# Mainboard.net
KiCad netlist of a schematic drawn in EAGLE
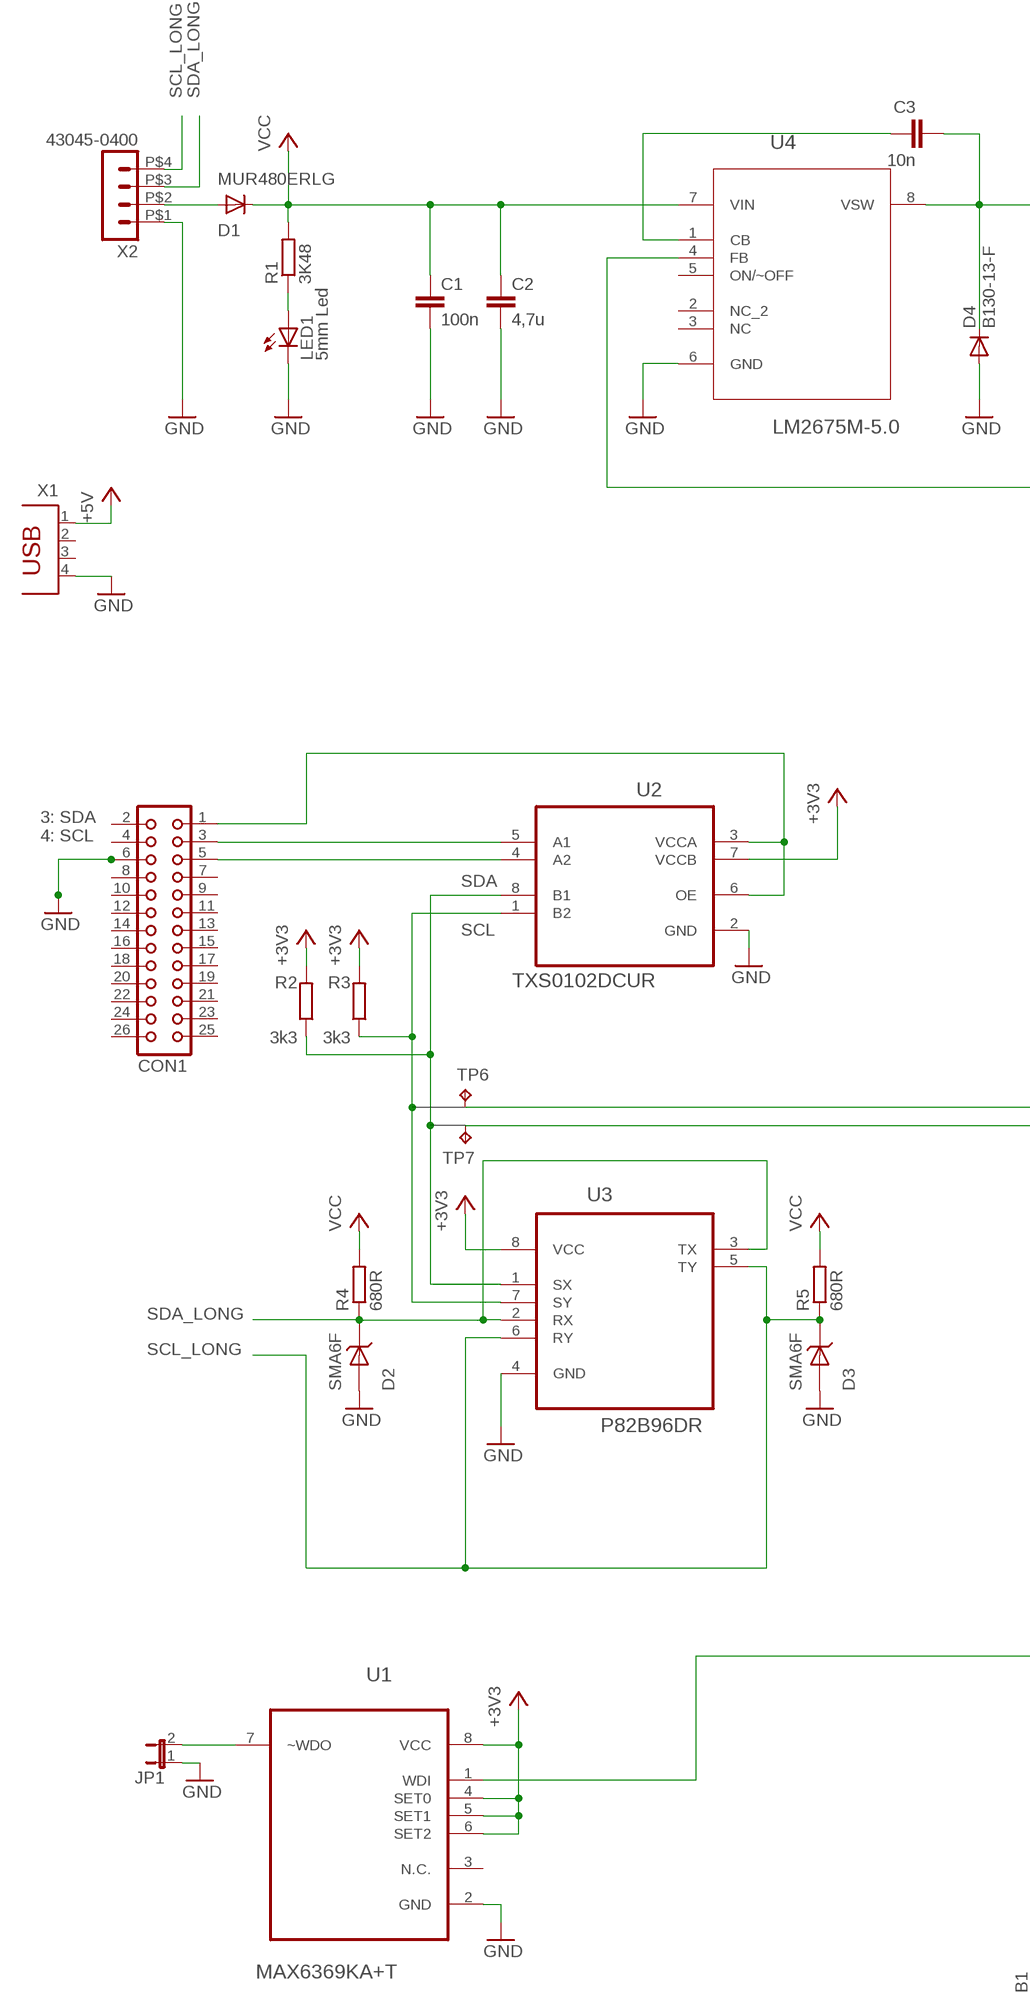
[diagram p0: schematic, sheet 1, part 1 of 2]
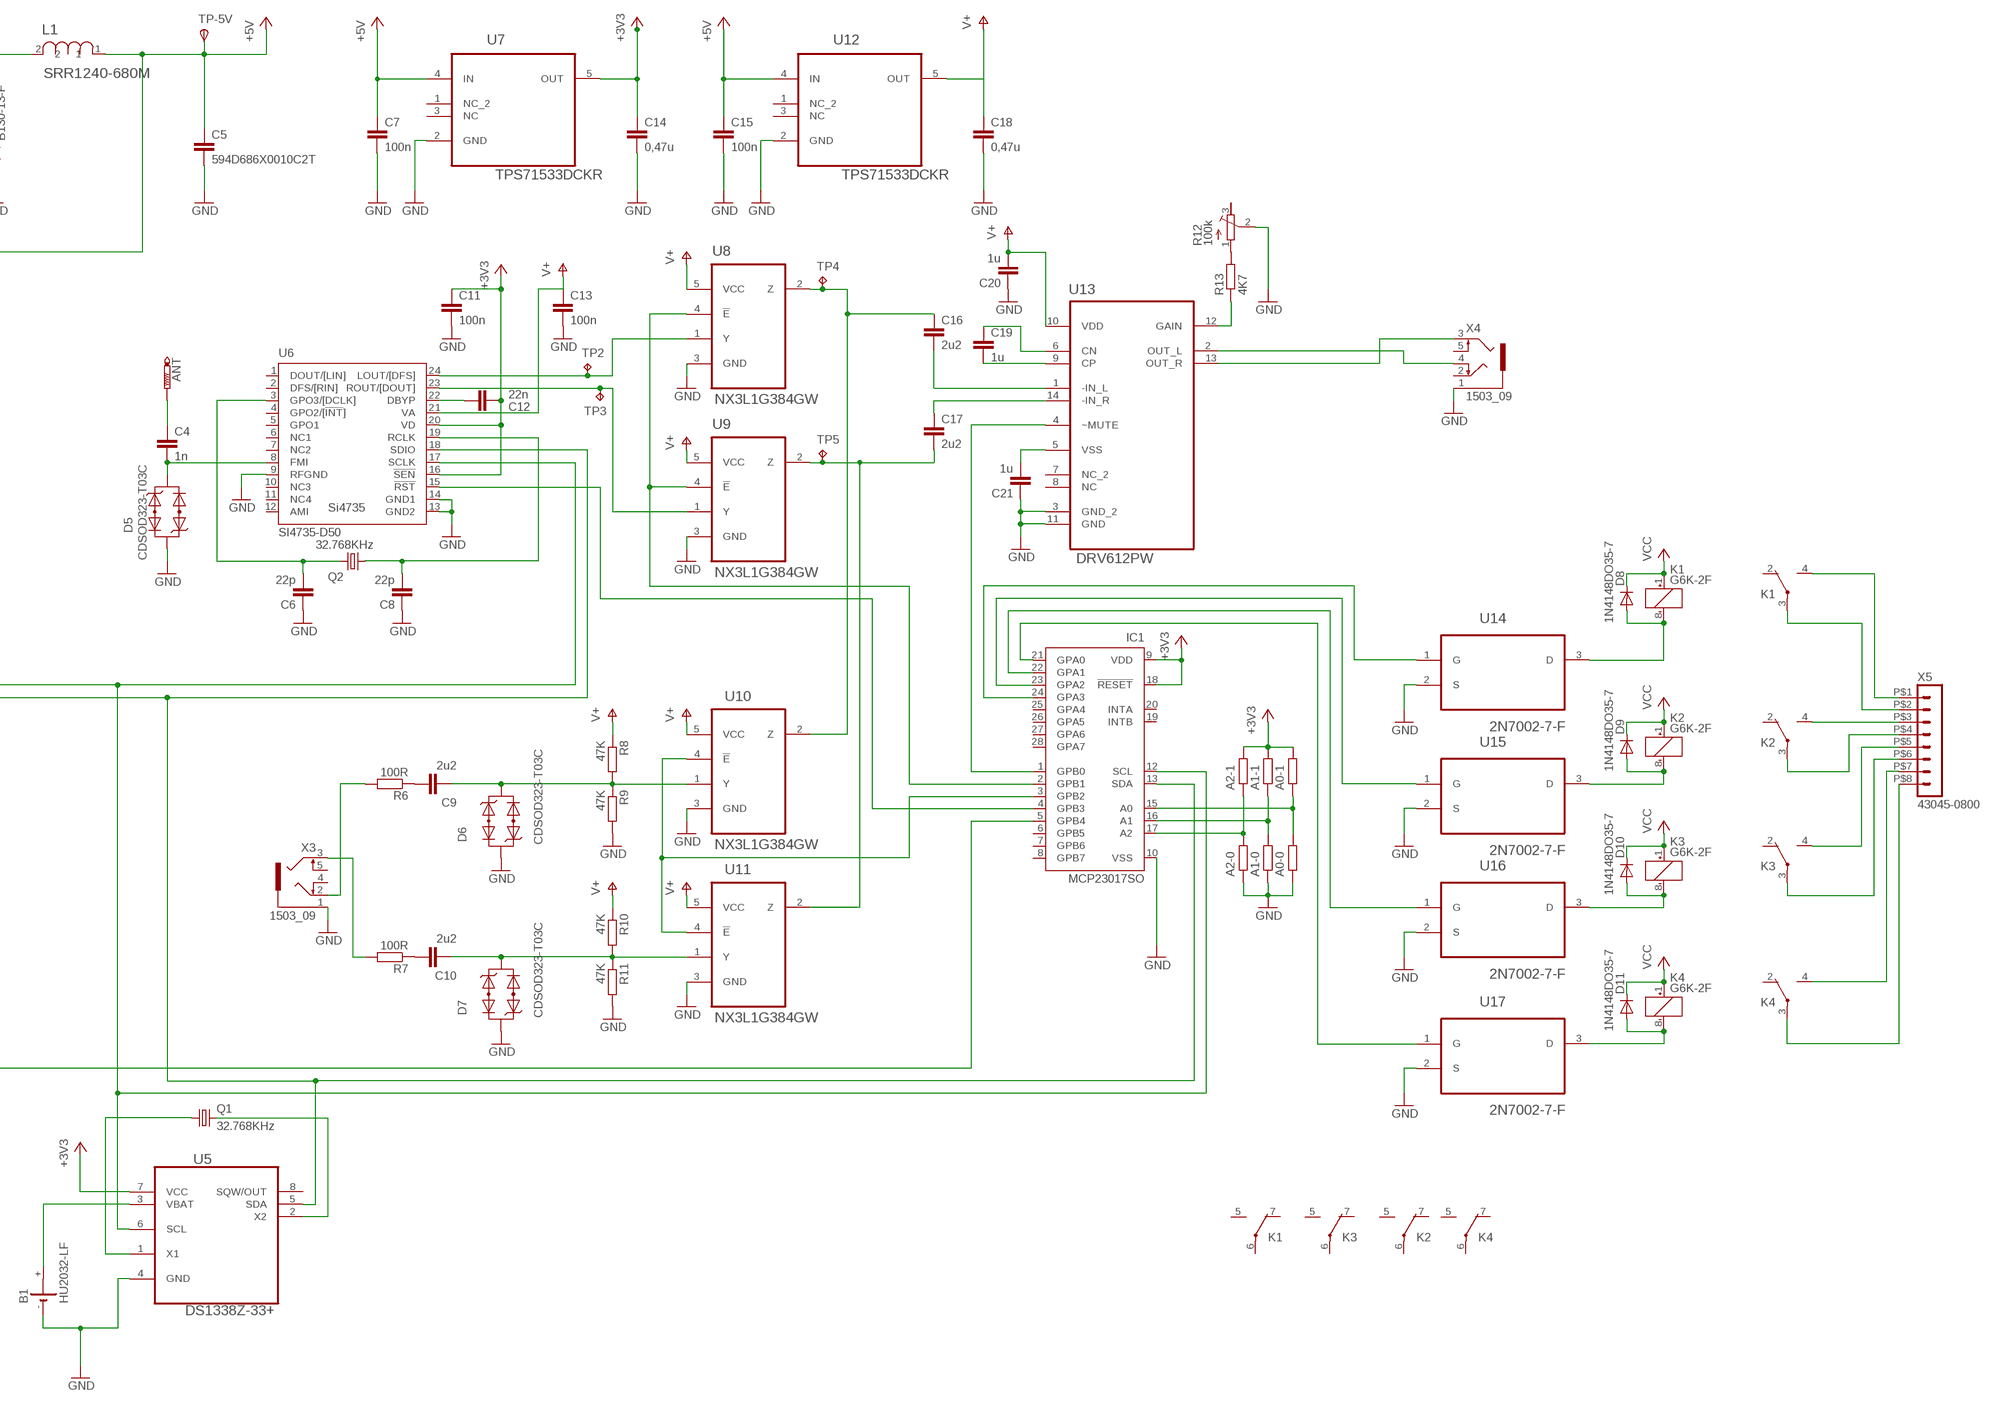
[diagram p1: schematic, sheet 1, part 2 of 2]

(export (version "E")
  (design (tool "Eeschema 10.0.6"))
  (components
    (comp (ref "ANT")
      (value "PTR1PAD1-13")
      (footprint "eagle-import:P1-13")
      (libsource (lib "eagle-import") (part "PTR1PAD1-13"))
    )
    (comp (ref "B1")
      (value "HU2032-LF")
      (footprint "eagle-import:HU2032-LF")
      (libsource (lib "eagle-import") (part "HU2032-LF"))
    )
    (comp (ref "C1")
      (value "100n")
      (footprint "eagle-import:C0805")
      (libsource (lib "eagle-import") (part "C-EUC0805"))
    )
    (comp (ref "C2")
      (value "4,7u")
      (footprint "eagle-import:C1206")
      (libsource (lib "eagle-import") (part "C-EUC1206"))
    )
    (comp (ref "C3")
      (value "10n")
      (footprint "eagle-import:C0805")
      (libsource (lib "eagle-import") (part "C-EUC0805"))
    )
    (comp (ref "C4")
      (value "1n")
      (footprint "eagle-import:C0402")
      (libsource (lib "eagle-import") (part "C-EUC0402"))
    )
    (comp (ref "C5")
      (value "594D686X0010C2T")
      (footprint "eagle-import:594D-B")
      (libsource (lib "eagle-import") (part "594D686X0010C2T"))
    )
    (comp (ref "C6")
      (value "22p")
      (footprint "eagle-import:C0402")
      (libsource (lib "eagle-import") (part "C-EUC0402"))
    )
    (comp (ref "C7")
      (value "100n")
      (footprint "eagle-import:C0805")
      (libsource (lib "eagle-import") (part "C-EUC0805"))
    )
    (comp (ref "C8")
      (value "22p")
      (footprint "eagle-import:C0402")
      (libsource (lib "eagle-import") (part "C-EUC0402"))
    )
    (comp (ref "C9")
      (value "2u2")
      (footprint "eagle-import:C0805")
      (libsource (lib "eagle-import") (part "C-EUC0805"))
    )
    (comp (ref "C10")
      (value "2u2")
      (footprint "eagle-import:C0805")
      (libsource (lib "eagle-import") (part "C-EUC0805"))
    )
    (comp (ref "C11")
      (value "100n")
      (footprint "eagle-import:C0805")
      (libsource (lib "eagle-import") (part "C-EUC0805"))
    )
    (comp (ref "C12")
      (value "22n")
      (footprint "eagle-import:C0805")
      (libsource (lib "eagle-import") (part "C-EUC0805"))
    )
    (comp (ref "C13")
      (value "100n")
      (footprint "eagle-import:C0805")
      (libsource (lib "eagle-import") (part "C-EUC0805"))
    )
    (comp (ref "C14")
      (value "0,47u")
      (footprint "eagle-import:C0805")
      (libsource (lib "eagle-import") (part "C-EUC0805"))
    )
    (comp (ref "C15")
      (value "100n")
      (footprint "eagle-import:C0805")
      (libsource (lib "eagle-import") (part "C-EUC0805"))
    )
    (comp (ref "C16")
      (value "2u2")
      (footprint "eagle-import:C0805")
      (libsource (lib "eagle-import") (part "C-EUC0805"))
    )
    (comp (ref "C17")
      (value "2u2")
      (footprint "eagle-import:C0805")
      (libsource (lib "eagle-import") (part "C-EUC0805"))
    )
    (comp (ref "C18")
      (value "0,47u")
      (footprint "eagle-import:C0805")
      (libsource (lib "eagle-import") (part "C-EUC0805"))
    )
    (comp (ref "C19")
      (value "1u")
      (footprint "eagle-import:C1005")
      (libsource (lib "eagle-import") (part "C-EUC1005"))
    )
    (comp (ref "C20")
      (value "1u")
      (footprint "eagle-import:C1005")
      (libsource (lib "eagle-import") (part "C-EUC1005"))
    )
    (comp (ref "C21")
      (value "1u")
      (footprint "eagle-import:C1005")
      (libsource (lib "eagle-import") (part "C-EUC1005"))
    )
    (comp (ref "CON1")
      (value "CON26")
      (footprint "eagle-import:CON26")
      (libsource (lib "eagle-import") (part "CON26"))
    )
    (comp (ref "D1")
      (value "MUR480ERLG")
      (footprint "eagle-import:DO41-10")
      (libsource (lib "eagle-import") (part "MUR150RL"))
    )
    (comp (ref "D2")
      (value "SMA6F")
      (footprint "eagle-import:DO-221AC")
      (libsource (lib "eagle-import") (part "SMA6F"))
    )
    (comp (ref "D3")
      (value "SMA6F")
      (footprint "eagle-import:DO-221AC")
      (libsource (lib "eagle-import") (part "SMA6F"))
    )
    (comp (ref "D4")
      (value "B130-13-F")
      (footprint "eagle-import:DO-214AC")
      (libsource (lib "eagle-import") (part "DIODE-DO-214AC"))
    )
    (comp (ref "D5")
      (value "CDSOD323-T03C")
      (footprint "eagle-import:SOD323")
      (libsource (lib "eagle-import") (part "CDSOD323-T03C"))
    )
    (comp (ref "D6")
      (value "CDSOD323-T03C")
      (footprint "eagle-import:SOD323")
      (libsource (lib "eagle-import") (part "CDSOD323-T03C"))
    )
    (comp (ref "D7")
      (value "CDSOD323-T03C")
      (footprint "eagle-import:SOD323")
      (libsource (lib "eagle-import") (part "CDSOD323-T03C"))
    )
    (comp (ref "D8")
      (value "1N4148DO35-7")
      (footprint "eagle-import:DO35-7")
      (libsource (lib "eagle-import") (part "1N4148DO35-7"))
    )
    (comp (ref "D9")
      (value "1N4148DO35-7")
      (footprint "eagle-import:DO35-7")
      (libsource (lib "eagle-import") (part "1N4148DO35-7"))
    )
    (comp (ref "D10")
      (value "1N4148DO35-7")
      (footprint "eagle-import:DO35-7")
      (libsource (lib "eagle-import") (part "1N4148DO35-7"))
    )
    (comp (ref "D11")
      (value "1N4148DO35-7")
      (footprint "eagle-import:DO35-7")
      (libsource (lib "eagle-import") (part "1N4148DO35-7"))
    )
    (comp (ref "IC1")
      (value "MCP23017SO")
      (footprint "eagle-import:SO28W")
      (fields (field (name "MF") "MICROCHIP") (field (name "MPN") "MCP23017-E/SO"))
      (libsource (lib "eagle-import") (part "MCP23017SO"))
    )
    (comp (ref "JP1")
      (value "JP1E")
      (footprint "eagle-import:JP1")
      (libsource (lib "eagle-import") (part "JP1E"))
    )
    (comp (ref "K1")
      (value "G6K-2F")
      (footprint "eagle-import:G6K-2F")
      (fields (field (name "MF") "OMRON COMPONENTS USA") (field (name "MPN") "G6K-2F DC24"))
      (libsource (lib "eagle-import") (part "G6K-2F"))
    )
    (comp (ref "K2")
      (value "G6K-2F")
      (footprint "eagle-import:G6K-2F")
      (fields (field (name "MF") "OMRON COMPONENTS USA") (field (name "MPN") "G6K-2F DC24"))
      (libsource (lib "eagle-import") (part "G6K-2F"))
    )
    (comp (ref "K3")
      (value "G6K-2F")
      (footprint "eagle-import:G6K-2F")
      (fields (field (name "MF") "OMRON COMPONENTS USA") (field (name "MPN") "G6K-2F DC24"))
      (libsource (lib "eagle-import") (part "G6K-2F"))
    )
    (comp (ref "K4")
      (value "G6K-2F")
      (footprint "eagle-import:G6K-2F")
      (fields (field (name "MF") "OMRON COMPONENTS USA") (field (name "MPN") "G6K-2F DC24"))
      (libsource (lib "eagle-import") (part "G6K-2F"))
    )
    (comp (ref "L1")
      (value "SRR1240-680M")
      (footprint "eagle-import:SRR1240")
      (libsource (lib "eagle-import") (part "SRR1240-680M"))
    )
    (comp (ref "LED1")
      (value "5mm Led")
      (footprint "eagle-import:LED5MM")
      (libsource (lib "eagle-import") (part "LED5MM"))
    )
    (comp (ref "Q1")
      (value "32.768KHz")
      (footprint "eagle-import:TC26V")
      (libsource (lib "eagle-import") (part "CRYSTALTC26V"))
    )
    (comp (ref "Q2")
      (value "32.768KHz")
      (footprint "eagle-import:TC26V")
      (libsource (lib "eagle-import") (part "CRYSTALTC26V"))
    )
    (comp (ref "R1")
      (value "3K48")
      (footprint "eagle-import:0204_7")
      (libsource (lib "eagle-import") (part "R-EU_0204/7"))
    )
    (comp (ref "R2")
      (value "3k3")
      (footprint "eagle-import:0204_5")
      (libsource (lib "eagle-import") (part "resistor_R-EU_0204/5"))
    )
    (comp (ref "R3")
      (value "3k3")
      (footprint "eagle-import:0204_5")
      (libsource (lib "eagle-import") (part "resistor_R-EU_0204/5"))
    )
    (comp (ref "R4")
      (value "680R")
      (footprint "eagle-import:0204V")
      (libsource (lib "eagle-import") (part "resistor_R-EU_0204/2V"))
    )
    (comp (ref "R5")
      (value "680R")
      (footprint "eagle-import:0204V")
      (libsource (lib "eagle-import") (part "resistor_R-EU_0204/2V"))
    )
    (comp (ref "R6")
      (value "100R")
      (footprint "eagle-import:0204V")
      (libsource (lib "eagle-import") (part "resistor_R-EU_0204/2V"))
    )
    (comp (ref "R7")
      (value "100R")
      (footprint "eagle-import:0204V")
      (libsource (lib "eagle-import") (part "resistor_R-EU_0204/2V"))
    )
    (comp (ref "R8")
      (value "47K")
      (footprint "eagle-import:0204V")
      (libsource (lib "eagle-import") (part "resistor_R-EU_0204/2V"))
    )
    (comp (ref "R9")
      (value "47K")
      (footprint "eagle-import:0204V")
      (libsource (lib "eagle-import") (part "resistor_R-EU_0204/2V"))
    )
    (comp (ref "R10")
      (value "47K")
      (footprint "eagle-import:0204V")
      (libsource (lib "eagle-import") (part "resistor_R-EU_0204/2V"))
    )
    (comp (ref "R11")
      (value "47K")
      (footprint "eagle-import:0204V")
      (libsource (lib "eagle-import") (part "resistor_R-EU_0204/2V"))
    )
    (comp (ref "R12")
      (value "100k")
      (footprint "eagle-import:RTRIM4G_J")
      (libsource (lib "eagle-import") (part "R-TRIMM4G/J"))
    )
    (comp (ref "R13")
      (value "4K7")
      (footprint "eagle-import:0204V")
      (libsource (lib "eagle-import") (part "resistor_R-EU_0204/2V"))
    )
    (comp (ref "R14")
      (value "A2-1")
      (footprint "eagle-import:R0402")
      (libsource (lib "eagle-import") (part "resistor_R-EU_R0402"))
    )
    (comp (ref "R15")
      (value "A2-0")
      (footprint "eagle-import:R0402")
      (libsource (lib "eagle-import") (part "resistor_R-EU_R0402"))
    )
    (comp (ref "R16")
      (value "A1-1")
      (footprint "eagle-import:R0402")
      (libsource (lib "eagle-import") (part "resistor_R-EU_R0402"))
    )
    (comp (ref "R17")
      (value "A1-0")
      (footprint "eagle-import:R0402")
      (libsource (lib "eagle-import") (part "resistor_R-EU_R0402"))
    )
    (comp (ref "R18")
      (value "A0-1")
      (footprint "eagle-import:R0402")
      (libsource (lib "eagle-import") (part "resistor_R-EU_R0402"))
    )
    (comp (ref "R19")
      (value "A0-0")
      (footprint "eagle-import:R0402")
      (libsource (lib "eagle-import") (part "resistor_R-EU_R0402"))
    )
    (comp (ref "TP-5V")
      (value "TPSTP10SQ")
      (footprint "eagle-import:TP10SQ")
      (libsource (lib "eagle-import") (part "TPSTP10SQ"))
    )
    (comp (ref "TP2")
      (value "TPTP07SQ")
      (footprint "eagle-import:TP07SQ")
      (libsource (lib "eagle-import") (part "TPTP07SQ"))
    )
    (comp (ref "TP3")
      (value "TPTP07SQ")
      (footprint "eagle-import:TP07SQ")
      (libsource (lib "eagle-import") (part "TPTP07SQ"))
    )
    (comp (ref "TP4")
      (value "TPTP07SQ")
      (footprint "eagle-import:TP07SQ")
      (libsource (lib "eagle-import") (part "TPTP07SQ"))
    )
    (comp (ref "TP5")
      (value "TPTP07SQ")
      (footprint "eagle-import:TP07SQ")
      (libsource (lib "eagle-import") (part "TPTP07SQ"))
    )
    (comp (ref "TP6")
      (value "TPTP07SQ")
      (footprint "eagle-import:TP07SQ")
      (libsource (lib "eagle-import") (part "TPTP07SQ"))
    )
    (comp (ref "TP7")
      (value "TPTP07SQ")
      (footprint "eagle-import:TP07SQ")
      (libsource (lib "eagle-import") (part "TPTP07SQ"))
    )
    (comp (ref "U1")
      (value "MAX6369KA+T")
      (footprint "eagle-import:SOT65P280X145-8N")
      (libsource (lib "eagle-import") (part "MAX6369KA+T"))
    )
    (comp (ref "U2")
      (value "TXS0102DCUR")
      (footprint "eagle-import:SOP50P310X90-8N")
      (libsource (lib "eagle-import") (part "TXS0102DCUR"))
    )
    (comp (ref "U3")
      (value "P82B96DR")
      (footprint "eagle-import:SOIC127P600X175-8N")
      (libsource (lib "eagle-import") (part "P82B96DR"))
    )
    (comp (ref "U4")
      (value "LM2675M-5.0")
      (footprint "eagle-import:SOIC127P620X175-8N")
      (libsource (lib "eagle-import") (part "LM2675M-5.0"))
    )
    (comp (ref "U5")
      (value "DS1338Z-33+")
      (footprint "eagle-import:SOIC127P600X175-8N")
      (libsource (lib "eagle-import") (part "DS1338Z-33+"))
    )
    (comp (ref "U6")
      (value "SI4735-D50")
      (footprint "eagle-import:SSOP24")
      (libsource (lib "eagle-import") (part "SI4735-D50"))
    )
    (comp (ref "U7")
      (value "TPS71533DCKR")
      (footprint "eagle-import:SOT65P210X110-5N")
      (libsource (lib "eagle-import") (part "TPS71533DCKR"))
    )
    (comp (ref "U8")
      (value "NX3L1G384GW")
      (footprint "eagle-import:SOT65P212X110-5N")
      (libsource (lib "eagle-import") (part "NX3L1G384GW"))
    )
    (comp (ref "U9")
      (value "NX3L1G384GW")
      (footprint "eagle-import:SOT65P212X110-5N")
      (libsource (lib "eagle-import") (part "NX3L1G384GW"))
    )
    (comp (ref "U10")
      (value "NX3L1G384GW")
      (footprint "eagle-import:SOT65P212X110-5N")
      (libsource (lib "eagle-import") (part "NX3L1G384GW"))
    )
    (comp (ref "U11")
      (value "NX3L1G384GW")
      (footprint "eagle-import:SOT65P212X110-5N")
      (libsource (lib "eagle-import") (part "NX3L1G384GW"))
    )
    (comp (ref "U12")
      (value "TPS71533DCKR")
      (footprint "eagle-import:SOT65P210X110-5N")
      (libsource (lib "eagle-import") (part "TPS71533DCKR"))
    )
    (comp (ref "U13")
      (value "DRV612PW")
      (footprint "eagle-import:SOP65P640X120-14N")
      (libsource (lib "eagle-import") (part "DRV612PW"))
    )
    (comp (ref "U14")
      (value "2N7002-7-F")
      (footprint "eagle-import:SOT103P240X110-3N")
      (libsource (lib "eagle-import") (part "2N7002-7-F"))
    )
    (comp (ref "U15")
      (value "2N7002-7-F")
      (footprint "eagle-import:SOT103P240X110-3N")
      (libsource (lib "eagle-import") (part "2N7002-7-F"))
    )
    (comp (ref "U16")
      (value "2N7002-7-F")
      (footprint "eagle-import:SOT103P240X110-3N")
      (libsource (lib "eagle-import") (part "2N7002-7-F"))
    )
    (comp (ref "U17")
      (value "2N7002-7-F")
      (footprint "eagle-import:SOT103P240X110-3N")
      (libsource (lib "eagle-import") (part "2N7002-7-F"))
    )
    (comp (ref "X1")
      (value "PN87520")
      (footprint "eagle-import:PN87520")
      (libsource (lib "eagle-import") (part "PN87520"))
    )
    (comp (ref "X2")
      (value "43045-0400")
      (footprint "eagle-import:43045-0400")
      (libsource (lib "eagle-import") (part "HEADER_POS4_?43045-0401"))
    )
    (comp (ref "X3")
      (value "1503_09")
      (footprint "eagle-import:1503_09")
      (libsource (lib "eagle-import") (part "1503_09"))
    )
    (comp (ref "X4")
      (value "1503_09")
      (footprint "eagle-import:1503_09")
      (libsource (lib "eagle-import") (part "1503_09"))
    )
    (comp (ref "X5")
      (value "43045-0800")
      (footprint "eagle-import:43045-0800")
      (libsource (lib "eagle-import") (part "HEADER_POS8_?43045-0800"))
    )
  )
  (nets
    (net (code "1") (name "+3V3") (class "Default")
      (node (ref "C11") (pin "1") (pinfunction "1_1") (pintype "passive"))
      (node (ref "C12") (pin "1") (pinfunction "1_1") (pintype "passive"))
      (node (ref "C14") (pin "1") (pinfunction "1_1") (pintype "passive"))
      (node (ref "IC1") (pin "18") (pinfunction "~{RESET}_18") (pintype "input"))
      (node (ref "IC1") (pin "9") (pinfunction "VDD_9") (pintype "power_in"))
      (node (ref "R14") (pin "2") (pinfunction "2_2") (pintype "passive"))
      (node (ref "R16") (pin "2") (pinfunction "2_2") (pintype "passive"))
      (node (ref "R18") (pin "2") (pinfunction "2_2") (pintype "passive"))
      (node (ref "R2") (pin "2") (pinfunction "2_2") (pintype "passive"))
      (node (ref "R3") (pin "2") (pinfunction "2_2") (pintype "passive"))
      (node (ref "U1") (pin "4") (pinfunction "SET0_4") (pintype "input"))
      (node (ref "U1") (pin "5") (pinfunction "SET1_5") (pintype "input"))
      (node (ref "U1") (pin "6") (pinfunction "SET2_6") (pintype "input"))
      (node (ref "U1") (pin "8") (pinfunction "VCC_8") (pintype "power_in"))
      (node (ref "U2") (pin "7") (pinfunction "VCCB_7") (pintype "power_in"))
      (node (ref "U3") (pin "8") (pinfunction "VCC_8") (pintype "power_in"))
      (node (ref "U5") (pin "7") (pinfunction "VCC_7") (pintype "power_in"))
      (node (ref "U6") (pin "16") (pinfunction "~{SEN}_16") (pintype "bidirectional"))
      (node (ref "U6") (pin "20") (pinfunction "VD_20") (pintype "power_in"))
      (node (ref "U7") (pin "5") (pinfunction "OUT_5") (pintype "output"))
    )
    (net (code "2") (name "+5V") (class "Default")
      (node (ref "C15") (pin "1") (pinfunction "1_1") (pintype "passive"))
      (node (ref "C5") (pin "P$1") (pinfunction "1_P$1") (pintype "passive"))
      (node (ref "C7") (pin "1") (pinfunction "1_1") (pintype "passive"))
      (node (ref "L1") (pin "1") (pinfunction "1_1") (pintype "passive"))
      (node (ref "TP-5V") (pin "TP") (pinfunction "PP_TP") (pintype "input"))
      (node (ref "U12") (pin "4") (pinfunction "IN_4") (pintype "power_in"))
      (node (ref "U4") (pin "4") (pinfunction "FB_4") (pintype "input"))
      (node (ref "U7") (pin "4") (pinfunction "IN_4") (pintype "power_in"))
      (node (ref "X1") (pin "1") (pinfunction "1_1") (pintype "passive"))
    )
    (net (code "3") (name "/SCL_LONG") (class "Default")
      (node (ref "D3") (pin "KAT") (pinfunction "KAT_KAT") (pintype "bidirectional"))
      (node (ref "R5") (pin "1") (pinfunction "1_1") (pintype "passive"))
      (node (ref "U3") (pin "5") (pinfunction "TY_5") (pintype "output"))
      (node (ref "U3") (pin "6") (pinfunction "RY_6") (pintype "input"))
      (node (ref "X2") (pin "P$4") (pinfunction "4_P$4") (pintype "passive"))
    )
    (net (code "4") (name "/SDA_LONG") (class "Default")
      (node (ref "D2") (pin "KAT") (pinfunction "KAT_KAT") (pintype "bidirectional"))
      (node (ref "R4") (pin "1") (pinfunction "1_1") (pintype "passive"))
      (node (ref "U3") (pin "2") (pinfunction "RX_2") (pintype "input"))
      (node (ref "U3") (pin "3") (pinfunction "TX_3") (pintype "output"))
      (node (ref "X2") (pin "P$3") (pinfunction "3_P$3") (pintype "passive"))
    )
    (net (code "5") (name "GND") (class "Default")
      (node (ref "B1") (pin "-") (pinfunction "-_-") (pintype "passive"))
      (node (ref "C1") (pin "2") (pinfunction "2_2") (pintype "passive"))
      (node (ref "C11") (pin "2") (pinfunction "2_2") (pintype "passive"))
      (node (ref "C13") (pin "2") (pinfunction "2_2") (pintype "passive"))
      (node (ref "C14") (pin "2") (pinfunction "2_2") (pintype "passive"))
      (node (ref "C15") (pin "2") (pinfunction "2_2") (pintype "passive"))
      (node (ref "C18") (pin "2") (pinfunction "2_2") (pintype "passive"))
      (node (ref "C2") (pin "2") (pinfunction "2_2") (pintype "passive"))
      (node (ref "C20") (pin "1") (pinfunction "1_1") (pintype "passive"))
      (node (ref "C21") (pin "1") (pinfunction "1_1") (pintype "passive"))
      (node (ref "C5") (pin "P$2") (pinfunction "2_P$2") (pintype "passive"))
      (node (ref "C6") (pin "1") (pinfunction "1_1") (pintype "passive"))
      (node (ref "C7") (pin "2") (pinfunction "2_2") (pintype "passive"))
      (node (ref "C8") (pin "1") (pinfunction "1_1") (pintype "passive"))
      (node (ref "CON1") (pin "6") (pinfunction "6_6") (pintype "passive"))
      (node (ref "D2") (pin "AN") (pinfunction "AN_AN") (pintype "bidirectional"))
      (node (ref "D3") (pin "AN") (pinfunction "AN_AN") (pintype "bidirectional"))
      (node (ref "D4") (pin "A") (pinfunction "A_A") (pintype "passive"))
      (node (ref "D5") (pin "P$1") (pinfunction "P$1_P$1") (pintype "bidirectional"))
      (node (ref "D6") (pin "P$1") (pinfunction "P$1_P$1") (pintype "bidirectional"))
      (node (ref "D7") (pin "P$1") (pinfunction "P$1_P$1") (pintype "bidirectional"))
      (node (ref "IC1") (pin "10") (pinfunction "VSS_10") (pintype "power_in"))
      (node (ref "JP1") (pin "1") (pinfunction "1_1") (pintype "passive"))
      (node (ref "LED1") (pin "K") (pinfunction "C_K") (pintype "passive"))
      (node (ref "R11") (pin "2") (pinfunction "2_2") (pintype "passive"))
      (node (ref "R12") (pin "2") (pinfunction "S_2") (pintype "passive"))
      (node (ref "R15") (pin "1") (pinfunction "1_1") (pintype "passive"))
      (node (ref "R17") (pin "1") (pinfunction "1_1") (pintype "passive"))
      (node (ref "R19") (pin "1") (pinfunction "1_1") (pintype "passive"))
      (node (ref "R9") (pin "2") (pinfunction "2_2") (pintype "passive"))
      (node (ref "U1") (pin "2") (pinfunction "GND_2") (pintype "passive"))
      (node (ref "U10") (pin "3") (pinfunction "GND_3") (pintype "passive"))
      (node (ref "U11") (pin "3") (pinfunction "GND_3") (pintype "passive"))
      (node (ref "U12") (pin "2") (pinfunction "GND_2") (pintype "passive"))
      (node (ref "U13") (pin "11") (pinfunction "GND_11") (pintype "passive"))
      (node (ref "U13") (pin "3") (pinfunction "GND_2_3") (pintype "passive"))
      (node (ref "U14") (pin "2") (pinfunction "S_2") (pintype "passive"))
      (node (ref "U15") (pin "2") (pinfunction "S_2") (pintype "passive"))
      (node (ref "U16") (pin "2") (pinfunction "S_2") (pintype "passive"))
      (node (ref "U17") (pin "2") (pinfunction "S_2") (pintype "passive"))
      (node (ref "U2") (pin "2") (pinfunction "GND_2") (pintype "passive"))
      (node (ref "U3") (pin "4") (pinfunction "GND_4") (pintype "passive"))
      (node (ref "U4") (pin "6") (pinfunction "GND_6") (pintype "passive"))
      (node (ref "U5") (pin "4") (pinfunction "GND_4") (pintype "passive"))
      (node (ref "U6") (pin "13") (pinfunction "GND2_13") (pintype "power_in"))
      (node (ref "U6") (pin "14") (pinfunction "GND1_14") (pintype "power_in"))
      (node (ref "U6") (pin "9") (pinfunction "RFGND_9") (pintype "bidirectional"))
      (node (ref "U7") (pin "2") (pinfunction "GND_2") (pintype "passive"))
      (node (ref "U8") (pin "3") (pinfunction "GND_3") (pintype "passive"))
      (node (ref "U9") (pin "3") (pinfunction "GND_3") (pintype "passive"))
      (node (ref "X1") (pin "4") (pinfunction "4_4") (pintype "passive"))
      (node (ref "X2") (pin "P$1") (pinfunction "1_P$1") (pintype "passive"))
      (node (ref "X3") (pin "1") (pinfunction "1_1") (pintype "passive"))
      (node (ref "X4") (pin "1") (pinfunction "1_1") (pintype "passive"))
    )
    (net (code "6") (name "Net-(ANT-PadTP)") (class "Default")
      (node (ref "ANT") (pin "TP") (pinfunction "TP_TP") (pintype "input"))
      (node (ref "C4") (pin "1") (pinfunction "1_1") (pintype "passive"))
    )
    (net (code "7") (name "Net-(C9-Pad1)") (class "Default")
      (node (ref "C9") (pin "1") (pinfunction "1_1") (pintype "passive"))
      (node (ref "R6") (pin "1") (pinfunction "1_1") (pintype "passive"))
    )
    (net (code "8") (name "Net-(C10-Pad1)") (class "Default")
      (node (ref "C10") (pin "1") (pinfunction "1_1") (pintype "passive"))
      (node (ref "R7") (pin "1") (pinfunction "1_1") (pintype "passive"))
    )
    (net (code "9") (name "Net-(IC1-A0)") (class "Default")
      (node (ref "IC1") (pin "15") (pinfunction "A0_15") (pintype "input"))
      (node (ref "R18") (pin "1") (pinfunction "1_1") (pintype "passive"))
      (node (ref "R19") (pin "2") (pinfunction "2_2") (pintype "passive"))
    )
    (net (code "10") (name "Net-(IC1-A1)") (class "Default")
      (node (ref "IC1") (pin "16") (pinfunction "A1_16") (pintype "input"))
      (node (ref "R16") (pin "1") (pinfunction "1_1") (pintype "passive"))
      (node (ref "R17") (pin "2") (pinfunction "2_2") (pintype "passive"))
    )
    (net (code "11") (name "Net-(IC1-A2)") (class "Default")
      (node (ref "IC1") (pin "17") (pinfunction "A2_17") (pintype "input"))
      (node (ref "R14") (pin "1") (pinfunction "1_1") (pintype "passive"))
      (node (ref "R15") (pin "2") (pinfunction "2_2") (pintype "passive"))
    )
    (net (code "12") (name "Net-(IC1-GPA0)") (class "Default")
      (node (ref "IC1") (pin "21") (pinfunction "GPA0_21") (pintype "bidirectional"))
      (node (ref "U17") (pin "1") (pinfunction "G_1") (pintype "input"))
    )
    (net (code "13") (name "Net-(IC1-GPA1)") (class "Default")
      (node (ref "IC1") (pin "22") (pinfunction "GPA1_22") (pintype "bidirectional"))
      (node (ref "U16") (pin "1") (pinfunction "G_1") (pintype "input"))
    )
    (net (code "14") (name "Net-(IC1-GPA2)") (class "Default")
      (node (ref "IC1") (pin "23") (pinfunction "GPA2_23") (pintype "bidirectional"))
      (node (ref "U15") (pin "1") (pinfunction "G_1") (pintype "input"))
    )
    (net (code "15") (name "Net-(IC1-GPA3)") (class "Default")
      (node (ref "IC1") (pin "24") (pinfunction "GPA3_24") (pintype "bidirectional"))
      (node (ref "U14") (pin "1") (pinfunction "G_1") (pintype "input"))
    )
    (net (code "16") (name "Net-(IC1-GPB0)") (class "Default")
      (node (ref "IC1") (pin "1") (pinfunction "GPB0_1") (pintype "bidirectional"))
      (node (ref "U13") (pin "4") (pinfunction "~{MUTE}_4") (pintype "input"))
    )
    (net (code "17") (name "Net-(IC1-GPB1)") (class "Default")
      (node (ref "IC1") (pin "2") (pinfunction "GPB1_2") (pintype "bidirectional"))
      (node (ref "U8") (pin "4") (pinfunction "~{E}_4") (pintype "input"))
      (node (ref "U9") (pin "4") (pinfunction "~{E}_4") (pintype "input"))
    )
    (net (code "18") (name "Net-(IC1-GPB2)") (class "Default")
      (node (ref "IC1") (pin "3") (pinfunction "GPB2_3") (pintype "bidirectional"))
      (node (ref "U10") (pin "4") (pinfunction "~{E}_4") (pintype "input"))
      (node (ref "U11") (pin "4") (pinfunction "~{E}_4") (pintype "input"))
    )
    (net (code "19") (name "Net-(IC1-GPB3)") (class "Default")
      (node (ref "IC1") (pin "4") (pinfunction "GPB3_4") (pintype "bidirectional"))
      (node (ref "U6") (pin "15") (pinfunction "~{RST}_15") (pintype "bidirectional"))
    )
    (net (code "20") (name "Net-(IC1-GPB4)") (class "Default")
      (node (ref "IC1") (pin "5") (pinfunction "GPB4_5") (pintype "bidirectional"))
      (node (ref "U1") (pin "1") (pinfunction "WDI_1") (pintype "input"))
    )
    (net (code "21") (name "Net-(IC1-SCL)") (class "Default")
      (node (ref "IC1") (pin "12") (pinfunction "SCL_12") (pintype "input"))
      (node (ref "TP6") (pin "TP") (pinfunction "TP_TP") (pintype "input"))
      (node (ref "U5") (pin "6") (pinfunction "SCL_6") (pintype "input"))
      (node (ref "U6") (pin "17") (pinfunction "SCLK_17") (pintype "bidirectional"))
    )
    (net (code "22") (name "Net-(IC1-SDA)") (class "Default")
      (node (ref "IC1") (pin "13") (pinfunction "SDA_13") (pintype "bidirectional"))
      (node (ref "TP7") (pin "TP") (pinfunction "TP_TP") (pintype "input"))
      (node (ref "U5") (pin "5") (pinfunction "SDA_5") (pintype "bidirectional"))
      (node (ref "U6") (pin "18") (pinfunction "SDIO_18") (pintype "bidirectional"))
    )
    (net (code "23") (name "Net-(K1A--)") (class "Default")
      (node (ref "D8") (pin "A") (pinfunction "A_A") (pintype "passive"))
      (node (ref "K1") (pin "8") (pinfunction "-_8") (pintype "passive"))
      (node (ref "U14") (pin "3") (pinfunction "D_3") (pintype "output"))
    )
    (net (code "24") (name "Net-(K1B-P)") (class "Default")
      (node (ref "K1") (pin "3") (pinfunction "P_3") (pintype "passive"))
      (node (ref "X5") (pin "P$2") (pinfunction "2_P$2") (pintype "passive"))
    )
    (net (code "25") (name "Net-(K1B-S)") (class "Default")
      (node (ref "K1") (pin "4") (pinfunction "S_4") (pintype "passive"))
      (node (ref "X5") (pin "P$1") (pinfunction "1_P$1") (pintype "passive"))
    )
    (net (code "26") (name "Net-(K2A--)") (class "Default")
      (node (ref "D9") (pin "A") (pinfunction "A_A") (pintype "passive"))
      (node (ref "K2") (pin "8") (pinfunction "-_8") (pintype "passive"))
      (node (ref "U15") (pin "3") (pinfunction "D_3") (pintype "output"))
    )
    (net (code "27") (name "Net-(K2B-P)") (class "Default")
      (node (ref "K2") (pin "3") (pinfunction "P_3") (pintype "passive"))
      (node (ref "X5") (pin "P$4") (pinfunction "4_P$4") (pintype "passive"))
    )
    (net (code "28") (name "Net-(K2B-S)") (class "Default")
      (node (ref "K2") (pin "4") (pinfunction "S_4") (pintype "passive"))
      (node (ref "X5") (pin "P$3") (pinfunction "3_P$3") (pintype "passive"))
    )
    (net (code "29") (name "Net-(K3A--)") (class "Default")
      (node (ref "D10") (pin "A") (pinfunction "A_A") (pintype "passive"))
      (node (ref "K3") (pin "8") (pinfunction "-_8") (pintype "passive"))
      (node (ref "U16") (pin "3") (pinfunction "D_3") (pintype "output"))
    )
    (net (code "30") (name "Net-(K3B-P)") (class "Default")
      (node (ref "K3") (pin "3") (pinfunction "P_3") (pintype "passive"))
      (node (ref "X5") (pin "P$6") (pinfunction "6_P$6") (pintype "passive"))
    )
    (net (code "31") (name "Net-(K3B-S)") (class "Default")
      (node (ref "K3") (pin "4") (pinfunction "S_4") (pintype "passive"))
      (node (ref "X5") (pin "P$5") (pinfunction "5_P$5") (pintype "passive"))
    )
    (net (code "32") (name "Net-(K4A--)") (class "Default")
      (node (ref "D11") (pin "A") (pinfunction "A_A") (pintype "passive"))
      (node (ref "K4") (pin "8") (pinfunction "-_8") (pintype "passive"))
      (node (ref "U17") (pin "3") (pinfunction "D_3") (pintype "output"))
    )
    (net (code "33") (name "Net-(K4B-P)") (class "Default")
      (node (ref "K4") (pin "3") (pinfunction "P_3") (pintype "passive"))
      (node (ref "X5") (pin "P$8") (pinfunction "8_P$8") (pintype "passive"))
    )
    (net (code "34") (name "Net-(K4B-S)") (class "Default")
      (node (ref "K4") (pin "4") (pinfunction "S_4") (pintype "passive"))
      (node (ref "X5") (pin "P$7") (pinfunction "7_P$7") (pintype "passive"))
    )
    (net (code "35") (name "Net-(LED1-PadA)") (class "Default")
      (node (ref "LED1") (pin "A") (pinfunction "A_A") (pintype "passive"))
      (node (ref "R1") (pin "1") (pinfunction "1_1") (pintype "passive"))
    )
    (net (code "36") (name "Net-(R6-Pad2)") (class "Default")
      (node (ref "R6") (pin "2") (pinfunction "2_2") (pintype "passive"))
      (node (ref "X3") (pin "2") (pinfunction "2_2") (pintype "passive"))
    )
    (net (code "37") (name "Net-(R7-Pad2)") (class "Default")
      (node (ref "R7") (pin "2") (pinfunction "2_2") (pintype "passive"))
      (node (ref "X3") (pin "3") (pinfunction "3_3") (pintype "passive"))
    )
    (net (code "38") (name "Net-(R12-E)") (class "Default")
      (node (ref "R12") (pin "1") (pinfunction "E_1") (pintype "passive"))
      (node (ref "R13") (pin "2") (pinfunction "2_2") (pintype "passive"))
    )
    (net (code "39") (name "Net-(U1-~{WDO})") (class "Default")
      (node (ref "JP1") (pin "2") (pinfunction "2_2") (pintype "passive"))
      (node (ref "U1") (pin "7") (pinfunction "~{WDO}_7") (pintype "output"))
    )
    (net (code "40") (name "Net-(U2-A1)") (class "Default")
      (node (ref "CON1") (pin "3") (pinfunction "3_3") (pintype "passive"))
      (node (ref "U2") (pin "5") (pinfunction "A1_5") (pintype "bidirectional"))
    )
    (net (code "41") (name "Net-(U2-A2)") (class "Default")
      (node (ref "CON1") (pin "5") (pinfunction "5_5") (pintype "passive"))
      (node (ref "U2") (pin "4") (pinfunction "A2_4") (pintype "bidirectional"))
    )
    (net (code "42") (name "Net-(U2-B1)") (class "Default")
      (node (ref "R2") (pin "1") (pinfunction "1_1") (pintype "passive"))
      (node (ref "U2") (pin "8") (pinfunction "B1_8") (pintype "bidirectional"))
      (node (ref "U3") (pin "1") (pinfunction "SX_1") (pintype "input"))
    )
    (net (code "43") (name "Net-(U2-B2)") (class "Default")
      (node (ref "R3") (pin "1") (pinfunction "1_1") (pintype "passive"))
      (node (ref "U2") (pin "1") (pinfunction "B2_1") (pintype "bidirectional"))
      (node (ref "U3") (pin "7") (pinfunction "SY_7") (pintype "input"))
    )
    (net (code "44") (name "Net-(U2-OE)") (class "Default")
      (node (ref "CON1") (pin "1") (pinfunction "1_1") (pintype "passive"))
      (node (ref "U2") (pin "3") (pinfunction "VCCA_3") (pintype "power_in"))
      (node (ref "U2") (pin "6") (pinfunction "OE_6") (pintype "input"))
    )
    (net (code "45") (name "Net-(U4-CB)") (class "Default")
      (node (ref "C3") (pin "1") (pinfunction "1_1") (pintype "passive"))
      (node (ref "U4") (pin "1") (pinfunction "CB_1") (pintype "input"))
    )
    (net (code "46") (name "Net-(U4-VSW)") (class "Default")
      (node (ref "C3") (pin "2") (pinfunction "2_2") (pintype "passive"))
      (node (ref "D4") (pin "C") (pinfunction "C_C") (pintype "passive"))
      (node (ref "L1") (pin "2") (pinfunction "2_2") (pintype "passive"))
      (node (ref "U4") (pin "8") (pinfunction "VSW_8") (pintype "output"))
    )
    (net (code "47") (name "Net-(U5-VBAT)") (class "Default")
      (node (ref "B1") (pin "+") (pinfunction "+_+") (pintype "passive"))
      (node (ref "U5") (pin "3") (pinfunction "VBAT_3") (pintype "power_in"))
    )
    (net (code "48") (name "Net-(U5-X1)") (class "Default")
      (node (ref "Q1") (pin "1") (pinfunction "1_1") (pintype "passive"))
      (node (ref "U5") (pin "1") (pinfunction "X1_1") (pintype "input"))
    )
    (net (code "49") (name "Net-(U5-X2)") (class "Default")
      (node (ref "Q1") (pin "2") (pinfunction "2_2") (pintype "passive"))
      (node (ref "U5") (pin "2") (pinfunction "X2_2") (pintype "output"))
    )
    (net (code "50") (name "Net-(U6-DBYP)") (class "Default")
      (node (ref "C12") (pin "2") (pinfunction "2_2") (pintype "passive"))
      (node (ref "U6") (pin "22") (pinfunction "DBYP_22") (pintype "bidirectional"))
    )
    (net (code "51") (name "Net-(U6-FMI)") (class "Default")
      (node (ref "C4") (pin "2") (pinfunction "2_2") (pintype "passive"))
      (node (ref "D5") (pin "P$2") (pinfunction "P$2_P$2") (pintype "bidirectional"))
      (node (ref "U6") (pin "8") (pinfunction "FMI_8") (pintype "bidirectional"))
    )
    (net (code "52") (name "Net-(U6-GPO3{slash}[DCLK])") (class "Default")
      (node (ref "C6") (pin "2") (pinfunction "2_2") (pintype "passive"))
      (node (ref "Q2") (pin "1") (pinfunction "1_1") (pintype "passive"))
      (node (ref "U6") (pin "3") (pinfunction "GPO3/[DCLK]_3") (pintype "bidirectional"))
    )
    (net (code "53") (name "Net-(U6-LOUT{slash}[DFS])") (class "Default")
      (node (ref "TP2") (pin "TP") (pinfunction "TP_TP") (pintype "input"))
      (node (ref "U6") (pin "24") (pinfunction "LOUT/[DFS]_24") (pintype "bidirectional"))
      (node (ref "U8") (pin "1") (pinfunction "Y_1") (pintype "bidirectional"))
    )
    (net (code "54") (name "Net-(U6-RCLK)") (class "Default")
      (node (ref "C8") (pin "2") (pinfunction "2_2") (pintype "passive"))
      (node (ref "Q2") (pin "2") (pinfunction "2_2") (pintype "passive"))
      (node (ref "U6") (pin "19") (pinfunction "RCLK_19") (pintype "bidirectional"))
    )
    (net (code "55") (name "Net-(U6-ROUT{slash}[DOUT])") (class "Default")
      (node (ref "TP3") (pin "TP") (pinfunction "TP_TP") (pintype "input"))
      (node (ref "U6") (pin "23") (pinfunction "ROUT/[DOUT]_23") (pintype "bidirectional"))
      (node (ref "U9") (pin "1") (pinfunction "Y_1") (pintype "bidirectional"))
    )
    (net (code "56") (name "Net-(U10-Y)") (class "Default")
      (node (ref "C9") (pin "2") (pinfunction "2_2") (pintype "passive"))
      (node (ref "D6") (pin "P$2") (pinfunction "P$2_P$2") (pintype "bidirectional"))
      (node (ref "R8") (pin "2") (pinfunction "2_2") (pintype "passive"))
      (node (ref "R9") (pin "1") (pinfunction "1_1") (pintype "passive"))
      (node (ref "U10") (pin "1") (pinfunction "Y_1") (pintype "bidirectional"))
    )
    (net (code "57") (name "Net-(U10-Z)") (class "Default")
      (node (ref "C16") (pin "1") (pinfunction "1_1") (pintype "passive"))
      (node (ref "TP4") (pin "TP") (pinfunction "TP_TP") (pintype "input"))
      (node (ref "U10") (pin "2") (pinfunction "Z_2") (pintype "bidirectional"))
      (node (ref "U8") (pin "2") (pinfunction "Z_2") (pintype "bidirectional"))
    )
    (net (code "58") (name "Net-(U11-Y)") (class "Default")
      (node (ref "C10") (pin "2") (pinfunction "2_2") (pintype "passive"))
      (node (ref "D7") (pin "P$2") (pinfunction "P$2_P$2") (pintype "bidirectional"))
      (node (ref "R10") (pin "2") (pinfunction "2_2") (pintype "passive"))
      (node (ref "R11") (pin "1") (pinfunction "1_1") (pintype "passive"))
      (node (ref "U11") (pin "1") (pinfunction "Y_1") (pintype "bidirectional"))
    )
    (net (code "59") (name "Net-(U11-Z)") (class "Default")
      (node (ref "C17") (pin "2") (pinfunction "2_2") (pintype "passive"))
      (node (ref "TP5") (pin "TP") (pinfunction "TP_TP") (pintype "input"))
      (node (ref "U11") (pin "2") (pinfunction "Z_2") (pintype "bidirectional"))
      (node (ref "U9") (pin "2") (pinfunction "Z_2") (pintype "bidirectional"))
    )
    (net (code "60") (name "Net-(U13--IN_L)") (class "Default")
      (node (ref "C16") (pin "2") (pinfunction "2_2") (pintype "passive"))
      (node (ref "U13") (pin "1") (pinfunction "-IN_L_1") (pintype "input"))
    )
    (net (code "61") (name "Net-(U13--IN_R)") (class "Default")
      (node (ref "C17") (pin "1") (pinfunction "1_1") (pintype "passive"))
      (node (ref "U13") (pin "14") (pinfunction "-IN_R_14") (pintype "input"))
    )
    (net (code "62") (name "Net-(U13-CN)") (class "Default")
      (node (ref "C19") (pin "1") (pinfunction "1_1") (pintype "passive"))
      (node (ref "U13") (pin "6") (pinfunction "CN_6") (pintype "bidirectional"))
    )
    (net (code "63") (name "Net-(U13-CP)") (class "Default")
      (node (ref "C19") (pin "2") (pinfunction "2_2") (pintype "passive"))
      (node (ref "U13") (pin "9") (pinfunction "CP_9") (pintype "bidirectional"))
    )
    (net (code "64") (name "Net-(U13-GAIN)") (class "Default")
      (node (ref "R13") (pin "1") (pinfunction "1_1") (pintype "passive"))
      (node (ref "U13") (pin "12") (pinfunction "GAIN_12") (pintype "input"))
    )
    (net (code "65") (name "Net-(U13-OUT_L)") (class "Default")
      (node (ref "U13") (pin "2") (pinfunction "OUT_L_2") (pintype "output"))
      (node (ref "X4") (pin "4") (pinfunction "4_4") (pintype "passive"))
    )
    (net (code "66") (name "Net-(U13-OUT_R)") (class "Default")
      (node (ref "U13") (pin "13") (pinfunction "OUT_R_13") (pintype "output"))
      (node (ref "X4") (pin "3") (pinfunction "3_3") (pintype "passive"))
    )
    (net (code "67") (name "Net-(U13-VSS)") (class "Default")
      (node (ref "C21") (pin "2") (pinfunction "2_2") (pintype "passive"))
      (node (ref "U13") (pin "5") (pinfunction "VSS_5") (pintype "power_in"))
    )
    (net (code "68") (name "Net-(X2-2)") (class "Default")
      (node (ref "D1") (pin "A") (pinfunction "A_A") (pintype "passive"))
      (node (ref "X2") (pin "P$2") (pinfunction "2_P$2") (pintype "passive"))
    )
    (net (code "69") (name "V+") (class "Default")
      (node (ref "C13") (pin "1") (pinfunction "1_1") (pintype "passive"))
      (node (ref "C18") (pin "1") (pinfunction "1_1") (pintype "passive"))
      (node (ref "C20") (pin "2") (pinfunction "2_2") (pintype "passive"))
      (node (ref "R10") (pin "1") (pinfunction "1_1") (pintype "passive"))
      (node (ref "R8") (pin "1") (pinfunction "1_1") (pintype "passive"))
      (node (ref "U10") (pin "5") (pinfunction "VCC_5") (pintype "power_in"))
      (node (ref "U11") (pin "5") (pinfunction "VCC_5") (pintype "power_in"))
      (node (ref "U12") (pin "5") (pinfunction "OUT_5") (pintype "output"))
      (node (ref "U13") (pin "10") (pinfunction "VDD_10") (pintype "power_in"))
      (node (ref "U6") (pin "21") (pinfunction "VA_21") (pintype "power_in"))
      (node (ref "U8") (pin "5") (pinfunction "VCC_5") (pintype "power_in"))
      (node (ref "U9") (pin "5") (pinfunction "VCC_5") (pintype "power_in"))
    )
    (net (code "70") (name "VCC") (class "Default")
      (node (ref "C1") (pin "1") (pinfunction "1_1") (pintype "passive"))
      (node (ref "C2") (pin "1") (pinfunction "1_1") (pintype "passive"))
      (node (ref "D1") (pin "C") (pinfunction "C_C") (pintype "passive"))
      (node (ref "D10") (pin "C") (pinfunction "C_C") (pintype "passive"))
      (node (ref "D11") (pin "C") (pinfunction "C_C") (pintype "passive"))
      (node (ref "D8") (pin "C") (pinfunction "C_C") (pintype "passive"))
      (node (ref "D9") (pin "C") (pinfunction "C_C") (pintype "passive"))
      (node (ref "K1") (pin "1") (pinfunction "+_1") (pintype "passive"))
      (node (ref "K2") (pin "1") (pinfunction "+_1") (pintype "passive"))
      (node (ref "K3") (pin "1") (pinfunction "+_1") (pintype "passive"))
      (node (ref "K4") (pin "1") (pinfunction "+_1") (pintype "passive"))
      (node (ref "R1") (pin "2") (pinfunction "2_2") (pintype "passive"))
      (node (ref "R4") (pin "2") (pinfunction "2_2") (pintype "passive"))
      (node (ref "R5") (pin "2") (pinfunction "2_2") (pintype "passive"))
      (node (ref "U4") (pin "7") (pinfunction "VIN_7") (pintype "power_in"))
    )
    (net (code "71") (name "unconnected-(B1-+-Pad+@1)") (class "Default")
      (node (ref "B1") (pin "+@1") (pinfunction "+_+@1") (pintype "passive"))
    )
    (net (code "72") (name "unconnected-(CON1-Pad2)") (class "Default")
      (node (ref "CON1") (pin "2") (pinfunction "2_2") (pintype "passive"))
    )
    (net (code "73") (name "unconnected-(CON1-Pad4)") (class "Default")
      (node (ref "CON1") (pin "4") (pinfunction "4_4") (pintype "passive"))
    )
    (net (code "74") (name "unconnected-(CON1-Pad7)") (class "Default")
      (node (ref "CON1") (pin "7") (pinfunction "7_7") (pintype "passive"))
    )
    (net (code "75") (name "unconnected-(CON1-Pad8)") (class "Default")
      (node (ref "CON1") (pin "8") (pinfunction "8_8") (pintype "passive"))
    )
    (net (code "76") (name "unconnected-(CON1-Pad9)") (class "Default")
      (node (ref "CON1") (pin "9") (pinfunction "9_9") (pintype "passive"))
    )
    (net (code "77") (name "unconnected-(CON1-Pad10)") (class "Default")
      (node (ref "CON1") (pin "10") (pinfunction "10_10") (pintype "passive"))
    )
    (net (code "78") (name "unconnected-(CON1-Pad11)") (class "Default")
      (node (ref "CON1") (pin "11") (pinfunction "11_11") (pintype "passive"))
    )
    (net (code "79") (name "unconnected-(CON1-Pad12)") (class "Default")
      (node (ref "CON1") (pin "12") (pinfunction "12_12") (pintype "passive"))
    )
    (net (code "80") (name "unconnected-(CON1-Pad13)") (class "Default")
      (node (ref "CON1") (pin "13") (pinfunction "13_13") (pintype "passive"))
    )
    (net (code "81") (name "unconnected-(CON1-Pad14)") (class "Default")
      (node (ref "CON1") (pin "14") (pinfunction "14_14") (pintype "passive"))
    )
    (net (code "82") (name "unconnected-(CON1-Pad15)") (class "Default")
      (node (ref "CON1") (pin "15") (pinfunction "15_15") (pintype "passive"))
    )
    (net (code "83") (name "unconnected-(CON1-Pad16)") (class "Default")
      (node (ref "CON1") (pin "16") (pinfunction "16_16") (pintype "passive"))
    )
    (net (code "84") (name "unconnected-(CON1-Pad17)") (class "Default")
      (node (ref "CON1") (pin "17") (pinfunction "17_17") (pintype "passive"))
    )
    (net (code "85") (name "unconnected-(CON1-Pad18)") (class "Default")
      (node (ref "CON1") (pin "18") (pinfunction "18_18") (pintype "passive"))
    )
    (net (code "86") (name "unconnected-(CON1-Pad19)") (class "Default")
      (node (ref "CON1") (pin "19") (pinfunction "19_19") (pintype "passive"))
    )
    (net (code "87") (name "unconnected-(CON1-Pad20)") (class "Default")
      (node (ref "CON1") (pin "20") (pinfunction "20_20") (pintype "passive"))
    )
    (net (code "88") (name "unconnected-(CON1-Pad21)") (class "Default")
      (node (ref "CON1") (pin "21") (pinfunction "21_21") (pintype "passive"))
    )
    (net (code "89") (name "unconnected-(CON1-Pad22)") (class "Default")
      (node (ref "CON1") (pin "22") (pinfunction "22_22") (pintype "passive"))
    )
    (net (code "90") (name "unconnected-(CON1-Pad23)") (class "Default")
      (node (ref "CON1") (pin "23") (pinfunction "23_23") (pintype "passive"))
    )
    (net (code "91") (name "unconnected-(CON1-Pad24)") (class "Default")
      (node (ref "CON1") (pin "24") (pinfunction "24_24") (pintype "passive"))
    )
    (net (code "92") (name "unconnected-(CON1-Pad25)") (class "Default")
      (node (ref "CON1") (pin "25") (pinfunction "25_25") (pintype "passive"))
    )
    (net (code "93") (name "unconnected-(CON1-Pad26)") (class "Default")
      (node (ref "CON1") (pin "26") (pinfunction "26_26") (pintype "passive"))
    )
    (net (code "94") (name "unconnected-(IC1-GPA4-Pad25)") (class "Default")
      (node (ref "IC1") (pin "25") (pinfunction "GPA4_25") (pintype "bidirectional"))
    )
    (net (code "95") (name "unconnected-(IC1-GPA5-Pad26)") (class "Default")
      (node (ref "IC1") (pin "26") (pinfunction "GPA5_26") (pintype "bidirectional"))
    )
    (net (code "96") (name "unconnected-(IC1-GPA6-Pad27)") (class "Default")
      (node (ref "IC1") (pin "27") (pinfunction "GPA6_27") (pintype "bidirectional"))
    )
    (net (code "97") (name "unconnected-(IC1-GPA7-Pad28)") (class "Default")
      (node (ref "IC1") (pin "28") (pinfunction "GPA7_28") (pintype "bidirectional"))
    )
    (net (code "98") (name "unconnected-(IC1-GPB5-Pad6)") (class "Default")
      (node (ref "IC1") (pin "6") (pinfunction "GPB5_6") (pintype "bidirectional"))
    )
    (net (code "99") (name "unconnected-(IC1-GPB6-Pad7)") (class "Default")
      (node (ref "IC1") (pin "7") (pinfunction "GPB6_7") (pintype "bidirectional"))
    )
    (net (code "100") (name "unconnected-(IC1-GPB7-Pad8)") (class "Default")
      (node (ref "IC1") (pin "8") (pinfunction "GPB7_8") (pintype "bidirectional"))
    )
    (net (code "101") (name "unconnected-(IC1-INTA-Pad20)") (class "Default")
      (node (ref "IC1") (pin "20") (pinfunction "INTA_20") (pintype "output"))
    )
    (net (code "102") (name "unconnected-(IC1-INTB-Pad19)") (class "Default")
      (node (ref "IC1") (pin "19") (pinfunction "INTB_19") (pintype "output"))
    )
    (net (code "103") (name "unconnected-(K1B-O-Pad2)") (class "Default")
      (node (ref "K1") (pin "2") (pinfunction "O_2") (pintype "passive"))
    )
    (net (code "104") (name "unconnected-(K1C-O-Pad7)") (class "Default")
      (node (ref "K1") (pin "7") (pinfunction "O_7") (pintype "passive"))
    )
    (net (code "105") (name "unconnected-(K1C-P-Pad6)") (class "Default")
      (node (ref "K1") (pin "6") (pinfunction "P_6") (pintype "passive"))
    )
    (net (code "106") (name "unconnected-(K1C-S-Pad5)") (class "Default")
      (node (ref "K1") (pin "5") (pinfunction "S_5") (pintype "passive"))
    )
    (net (code "107") (name "unconnected-(K2B-O-Pad2)") (class "Default")
      (node (ref "K2") (pin "2") (pinfunction "O_2") (pintype "passive"))
    )
    (net (code "108") (name "unconnected-(K2C-O-Pad7)") (class "Default")
      (node (ref "K2") (pin "7") (pinfunction "O_7") (pintype "passive"))
    )
    (net (code "109") (name "unconnected-(K2C-P-Pad6)") (class "Default")
      (node (ref "K2") (pin "6") (pinfunction "P_6") (pintype "passive"))
    )
    (net (code "110") (name "unconnected-(K2C-S-Pad5)") (class "Default")
      (node (ref "K2") (pin "5") (pinfunction "S_5") (pintype "passive"))
    )
    (net (code "111") (name "unconnected-(K3B-O-Pad2)") (class "Default")
      (node (ref "K3") (pin "2") (pinfunction "O_2") (pintype "passive"))
    )
    (net (code "112") (name "unconnected-(K3C-O-Pad7)") (class "Default")
      (node (ref "K3") (pin "7") (pinfunction "O_7") (pintype "passive"))
    )
    (net (code "113") (name "unconnected-(K3C-P-Pad6)") (class "Default")
      (node (ref "K3") (pin "6") (pinfunction "P_6") (pintype "passive"))
    )
    (net (code "114") (name "unconnected-(K3C-S-Pad5)") (class "Default")
      (node (ref "K3") (pin "5") (pinfunction "S_5") (pintype "passive"))
    )
    (net (code "115") (name "unconnected-(K4B-O-Pad2)") (class "Default")
      (node (ref "K4") (pin "2") (pinfunction "O_2") (pintype "passive"))
    )
    (net (code "116") (name "unconnected-(K4C-O-Pad7)") (class "Default")
      (node (ref "K4") (pin "7") (pinfunction "O_7") (pintype "passive"))
    )
    (net (code "117") (name "unconnected-(K4C-P-Pad6)") (class "Default")
      (node (ref "K4") (pin "6") (pinfunction "P_6") (pintype "passive"))
    )
    (net (code "118") (name "unconnected-(K4C-S-Pad5)") (class "Default")
      (node (ref "K4") (pin "5") (pinfunction "S_5") (pintype "passive"))
    )
    (net (code "119") (name "unconnected-(R12-A-Pad3)") (class "Default")
      (node (ref "R12") (pin "3") (pinfunction "A_3") (pintype "passive"))
    )
    (net (code "120") (name "unconnected-(U1-N.C.-Pad3)") (class "Default")
      (node (ref "U1") (pin "3") (pinfunction "N.C._3") (pintype "no_connect"))
    )
    (net (code "121") (name "unconnected-(U4-NC-Pad3)") (class "Default")
      (node (ref "U4") (pin "3") (pinfunction "NC_3") (pintype "no_connect"))
    )
    (net (code "122") (name "unconnected-(U4-NC_2-Pad2)") (class "Default")
      (node (ref "U4") (pin "2") (pinfunction "NC_2_2") (pintype "no_connect"))
    )
    (net (code "123") (name "unconnected-(U4-ON{slash}~{OFF}-Pad5)") (class "Default")
      (node (ref "U4") (pin "5") (pinfunction "ON/~{OFF}_5") (pintype "input"))
    )
    (net (code "124") (name "unconnected-(U5-SQW{slash}OUT-Pad8)") (class "Default")
      (node (ref "U5") (pin "8") (pinfunction "SQW/OUT_8") (pintype "output"))
    )
    (net (code "125") (name "unconnected-(U6-AMI-Pad12)") (class "Default")
      (node (ref "U6") (pin "12") (pinfunction "AMI_12") (pintype "bidirectional"))
    )
    (net (code "126") (name "unconnected-(U6-DFS{slash}[RIN]-Pad2)") (class "Default")
      (node (ref "U6") (pin "2") (pinfunction "DFS/[RIN]_2") (pintype "bidirectional"))
    )
    (net (code "127") (name "unconnected-(U6-DOUT{slash}[LIN]-Pad1)") (class "Default")
      (node (ref "U6") (pin "1") (pinfunction "DOUT/[LIN]_1") (pintype "bidirectional"))
    )
    (net (code "128") (name "unconnected-(U6-GPO1-Pad5)") (class "Default")
      (node (ref "U6") (pin "5") (pinfunction "GPO1_5") (pintype "bidirectional"))
    )
    (net (code "129") (name "unconnected-(U6-GPO2{slash}[~{INT}]-Pad4)") (class "Default")
      (node (ref "U6") (pin "4") (pinfunction "GPO2/[~{INT}]_4") (pintype "bidirectional"))
    )
    (net (code "130") (name "unconnected-(U6-NC1-Pad6)") (class "Default")
      (node (ref "U6") (pin "6") (pinfunction "NC1_6") (pintype "no_connect"))
    )
    (net (code "131") (name "unconnected-(U6-NC2-Pad7)") (class "Default")
      (node (ref "U6") (pin "7") (pinfunction "NC2_7") (pintype "no_connect"))
    )
    (net (code "132") (name "unconnected-(U6-NC3-Pad10)") (class "Default")
      (node (ref "U6") (pin "10") (pinfunction "NC3_10") (pintype "no_connect"))
    )
    (net (code "133") (name "unconnected-(U6-NC4-Pad11)") (class "Default")
      (node (ref "U6") (pin "11") (pinfunction "NC4_11") (pintype "no_connect"))
    )
    (net (code "134") (name "unconnected-(U7-NC-Pad3)") (class "Default")
      (node (ref "U7") (pin "3") (pinfunction "NC_3") (pintype "no_connect"))
    )
    (net (code "135") (name "unconnected-(U7-NC_2-Pad1)") (class "Default")
      (node (ref "U7") (pin "1") (pinfunction "NC_2_1") (pintype "no_connect"))
    )
    (net (code "136") (name "unconnected-(U12-NC-Pad3)") (class "Default")
      (node (ref "U12") (pin "3") (pinfunction "NC_3") (pintype "no_connect"))
    )
    (net (code "137") (name "unconnected-(U12-NC_2-Pad1)") (class "Default")
      (node (ref "U12") (pin "1") (pinfunction "NC_2_1") (pintype "no_connect"))
    )
    (net (code "138") (name "unconnected-(U13-NC-Pad8)") (class "Default")
      (node (ref "U13") (pin "8") (pinfunction "NC_8") (pintype "no_connect"))
    )
    (net (code "139") (name "unconnected-(U13-NC_2-Pad7)") (class "Default")
      (node (ref "U13") (pin "7") (pinfunction "NC_2_7") (pintype "no_connect"))
    )
    (net (code "140") (name "unconnected-(X1-Pad2)") (class "Default")
      (node (ref "X1") (pin "2") (pinfunction "2_2") (pintype "passive"))
    )
    (net (code "141") (name "unconnected-(X1-Pad3)") (class "Default")
      (node (ref "X1") (pin "3") (pinfunction "3_3") (pintype "passive"))
    )
    (net (code "142") (name "unconnected-(X3-Pad4)") (class "Default")
      (node (ref "X3") (pin "4") (pinfunction "4_4") (pintype "passive"))
    )
    (net (code "143") (name "unconnected-(X3-Pad5)") (class "Default")
      (node (ref "X3") (pin "5") (pinfunction "5_5") (pintype "passive"))
    )
    (net (code "144") (name "unconnected-(X4-Pad2)") (class "Default")
      (node (ref "X4") (pin "2") (pinfunction "2_2") (pintype "passive"))
    )
    (net (code "145") (name "unconnected-(X4-Pad5)") (class "Default")
      (node (ref "X4") (pin "5") (pinfunction "5_5") (pintype "passive"))
    )
  )
)
